# OpAmpBreakout-fragmentD.net
KiCad netlist of a schematic drawn in EAGLE
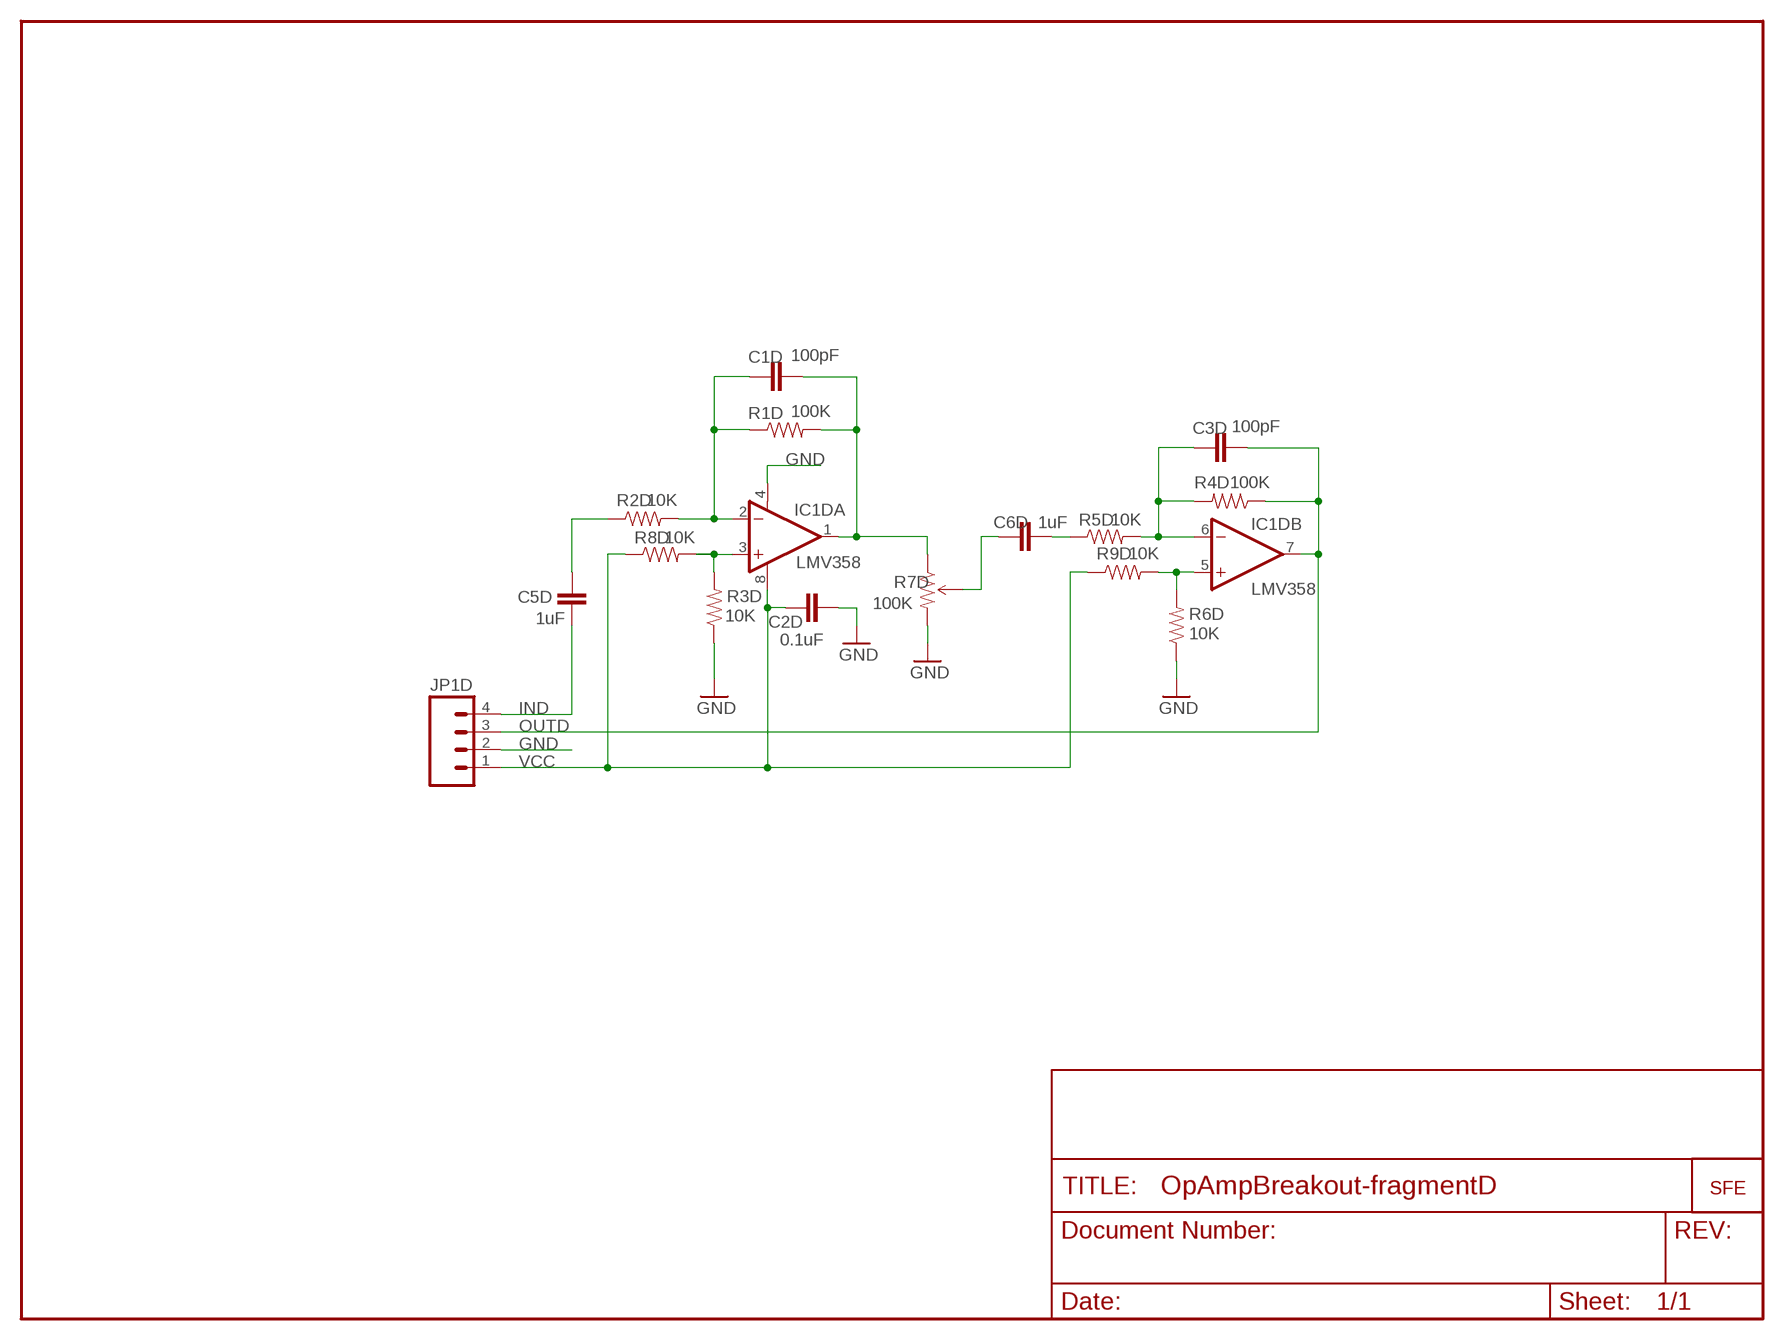
[diagram p0: schematic, sheet 1]

(export (version "E")
  (design (tool "Eeschema 10.0.6"))
  (components
    (comp (ref "C1D")
      (value "100pF")
      (footprint "eagle-import:C0402")
      (libsource (lib "eagle-import") (part "CAP0402"))
    )
    (comp (ref "C2D")
      (value "0.1uF")
      (footprint "eagle-import:C0402")
      (libsource (lib "eagle-import") (part "CAP0402"))
    )
    (comp (ref "C3D")
      (value "100pF")
      (footprint "eagle-import:C0402")
      (libsource (lib "eagle-import") (part "CAP0402"))
    )
    (comp (ref "C5D")
      (value "1uF")
      (footprint "eagle-import:C0402")
      (libsource (lib "eagle-import") (part "CAP0402"))
    )
    (comp (ref "C6D")
      (value "1uF")
      (footprint "eagle-import:C0402")
      (libsource (lib "eagle-import") (part "CAP0402"))
    )
    (comp (ref "IC1D")
      (value "LMV358")
      (footprint "eagle-import:SO08")
      (libsource (lib "eagle-import") (part "OPAMP-DUALU"))
    )
    (comp (ref "JP1D")
      (value "M04PTH")
      (footprint "eagle-import:1X04")
      (libsource (lib "eagle-import") (part "M04PTH"))
    )
    (comp (ref "R1D")
      (value "100K")
      (footprint "eagle-import:C0402")
      (libsource (lib "eagle-import") (part "RESISTOR0402"))
    )
    (comp (ref "R2D")
      (value "10K")
      (footprint "eagle-import:C0402")
      (libsource (lib "eagle-import") (part "RESISTOR0402"))
    )
    (comp (ref "R3D")
      (value "10K")
      (footprint "eagle-import:C0402")
      (libsource (lib "eagle-import") (part "RESISTOR0402"))
    )
    (comp (ref "R4D")
      (value "100K")
      (footprint "eagle-import:C0402")
      (libsource (lib "eagle-import") (part "RESISTOR0402"))
    )
    (comp (ref "R5D")
      (value "10K")
      (footprint "eagle-import:C0402")
      (libsource (lib "eagle-import") (part "RESISTOR0402"))
    )
    (comp (ref "R6D")
      (value "10K")
      (footprint "eagle-import:C0402")
      (libsource (lib "eagle-import") (part "RESISTOR0402"))
    )
    (comp (ref "R7D")
      (value "100K")
      (footprint "eagle-import:TRIMPOT-3MM")
      (libsource (lib "eagle-import") (part "TRIMPOTSMD"))
    )
    (comp (ref "R8D")
      (value "10K")
      (footprint "eagle-import:C0402")
      (libsource (lib "eagle-import") (part "SparkFun-DC_RESISTOR0402"))
    )
    (comp (ref "R9D")
      (value "10K")
      (footprint "eagle-import:C0402")
      (libsource (lib "eagle-import") (part "SparkFun-DC_RESISTOR0402"))
    )
    (comp (ref "U$3D")
      (value "LOGO-SFENEW")
      (footprint "eagle-import:SFE-NEW-WEBLOGO")
      (libsource (lib "eagle-import") (part "LOGO-SFENEW"))
    )
  )
  (nets
    (net (code "1") (name "/IND") (class "Default")
      (node (ref "C5D") (pin "1") (pinfunction "1_1") (pintype "passive"))
      (node (ref "JP1D") (pin "4") (pinfunction "4_4") (pintype "passive"))
    )
    (net (code "2") (name "/OUTD") (class "Default")
      (node (ref "C3D") (pin "2") (pinfunction "2_2") (pintype "passive"))
      (node (ref "IC1D") (pin "7") (pinfunction "OUT_7") (pintype "output"))
      (node (ref "JP1D") (pin "3") (pinfunction "3_3") (pintype "passive"))
      (node (ref "R4D") (pin "1") (pinfunction "1_1") (pintype "passive"))
    )
    (net (code "3") (name "/VCC") (class "Default")
      (node (ref "C2D") (pin "1") (pinfunction "1_1") (pintype "passive"))
      (node (ref "IC1D") (pin "8") (pinfunction "V+_8") (pintype "power_in"))
      (node (ref "JP1D") (pin "1") (pinfunction "1_1") (pintype "passive"))
      (node (ref "R8D") (pin "1") (pinfunction "1_1") (pintype "passive"))
      (node (ref "R9D") (pin "1") (pinfunction "1_1") (pintype "passive"))
    )
    (net (code "4") (name "GND") (class "Default")
      (node (ref "C2D") (pin "2") (pinfunction "2_2") (pintype "passive"))
      (node (ref "IC1D") (pin "4") (pinfunction "V-_4") (pintype "power_in"))
      (node (ref "JP1D") (pin "2") (pinfunction "2_2") (pintype "passive"))
      (node (ref "R3D") (pin "1") (pinfunction "1_1") (pintype "passive"))
      (node (ref "R6D") (pin "1") (pinfunction "1_1") (pintype "passive"))
      (node (ref "R7D") (pin "3") (pinfunction "CW_3") (pintype "passive"))
    )
    (net (code "5") (name "Net-(C5D-Pad2)") (class "Default")
      (node (ref "C5D") (pin "2") (pinfunction "2_2") (pintype "passive"))
      (node (ref "R2D") (pin "1") (pinfunction "1_1") (pintype "passive"))
    )
    (net (code "6") (name "Net-(C6D-Pad1)") (class "Default")
      (node (ref "C6D") (pin "1") (pinfunction "1_1") (pintype "passive"))
      (node (ref "R5D") (pin "1") (pinfunction "1_1") (pintype "passive"))
    )
    (net (code "7") (name "Net-(IC1DA-+IN)") (class "Default")
      (node (ref "IC1D") (pin "3") (pinfunction "+IN_3") (pintype "input"))
      (node (ref "R3D") (pin "2") (pinfunction "2_2") (pintype "passive"))
      (node (ref "R8D") (pin "2") (pinfunction "2_2") (pintype "passive"))
    )
    (net (code "8") (name "Net-(IC1DA--IN)") (class "Default")
      (node (ref "C1D") (pin "1") (pinfunction "1_1") (pintype "passive"))
      (node (ref "IC1D") (pin "2") (pinfunction "-IN_2") (pintype "input"))
      (node (ref "R1D") (pin "1") (pinfunction "1_1") (pintype "passive"))
      (node (ref "R2D") (pin "2") (pinfunction "2_2") (pintype "passive"))
    )
    (net (code "9") (name "Net-(IC1DA-OUT)") (class "Default")
      (node (ref "C1D") (pin "2") (pinfunction "2_2") (pintype "passive"))
      (node (ref "IC1D") (pin "1") (pinfunction "OUT_1") (pintype "output"))
      (node (ref "R1D") (pin "2") (pinfunction "2_2") (pintype "passive"))
      (node (ref "R7D") (pin "1") (pinfunction "CCW_1") (pintype "passive"))
    )
    (net (code "10") (name "Net-(IC1DB-+IN)") (class "Default")
      (node (ref "IC1D") (pin "5") (pinfunction "+IN_5") (pintype "input"))
      (node (ref "R6D") (pin "2") (pinfunction "2_2") (pintype "passive"))
      (node (ref "R9D") (pin "2") (pinfunction "2_2") (pintype "passive"))
    )
    (net (code "11") (name "Net-(IC1DB--IN)") (class "Default")
      (node (ref "C3D") (pin "1") (pinfunction "1_1") (pintype "passive"))
      (node (ref "IC1D") (pin "6") (pinfunction "-IN_6") (pintype "input"))
      (node (ref "R4D") (pin "2") (pinfunction "2_2") (pintype "passive"))
      (node (ref "R5D") (pin "2") (pinfunction "2_2") (pintype "passive"))
    )
    (net (code "12") (name "Net-(R7D-WIPER)") (class "Default")
      (node (ref "C6D") (pin "2") (pinfunction "2_2") (pintype "passive"))
      (node (ref "R7D") (pin "2") (pinfunction "WIPER_2") (pintype "passive"))
    )
  )
)
